# 12_-_MIPI-LVDS-RGB.net
KiCad netlist of a schematic drawn in Altium Designer
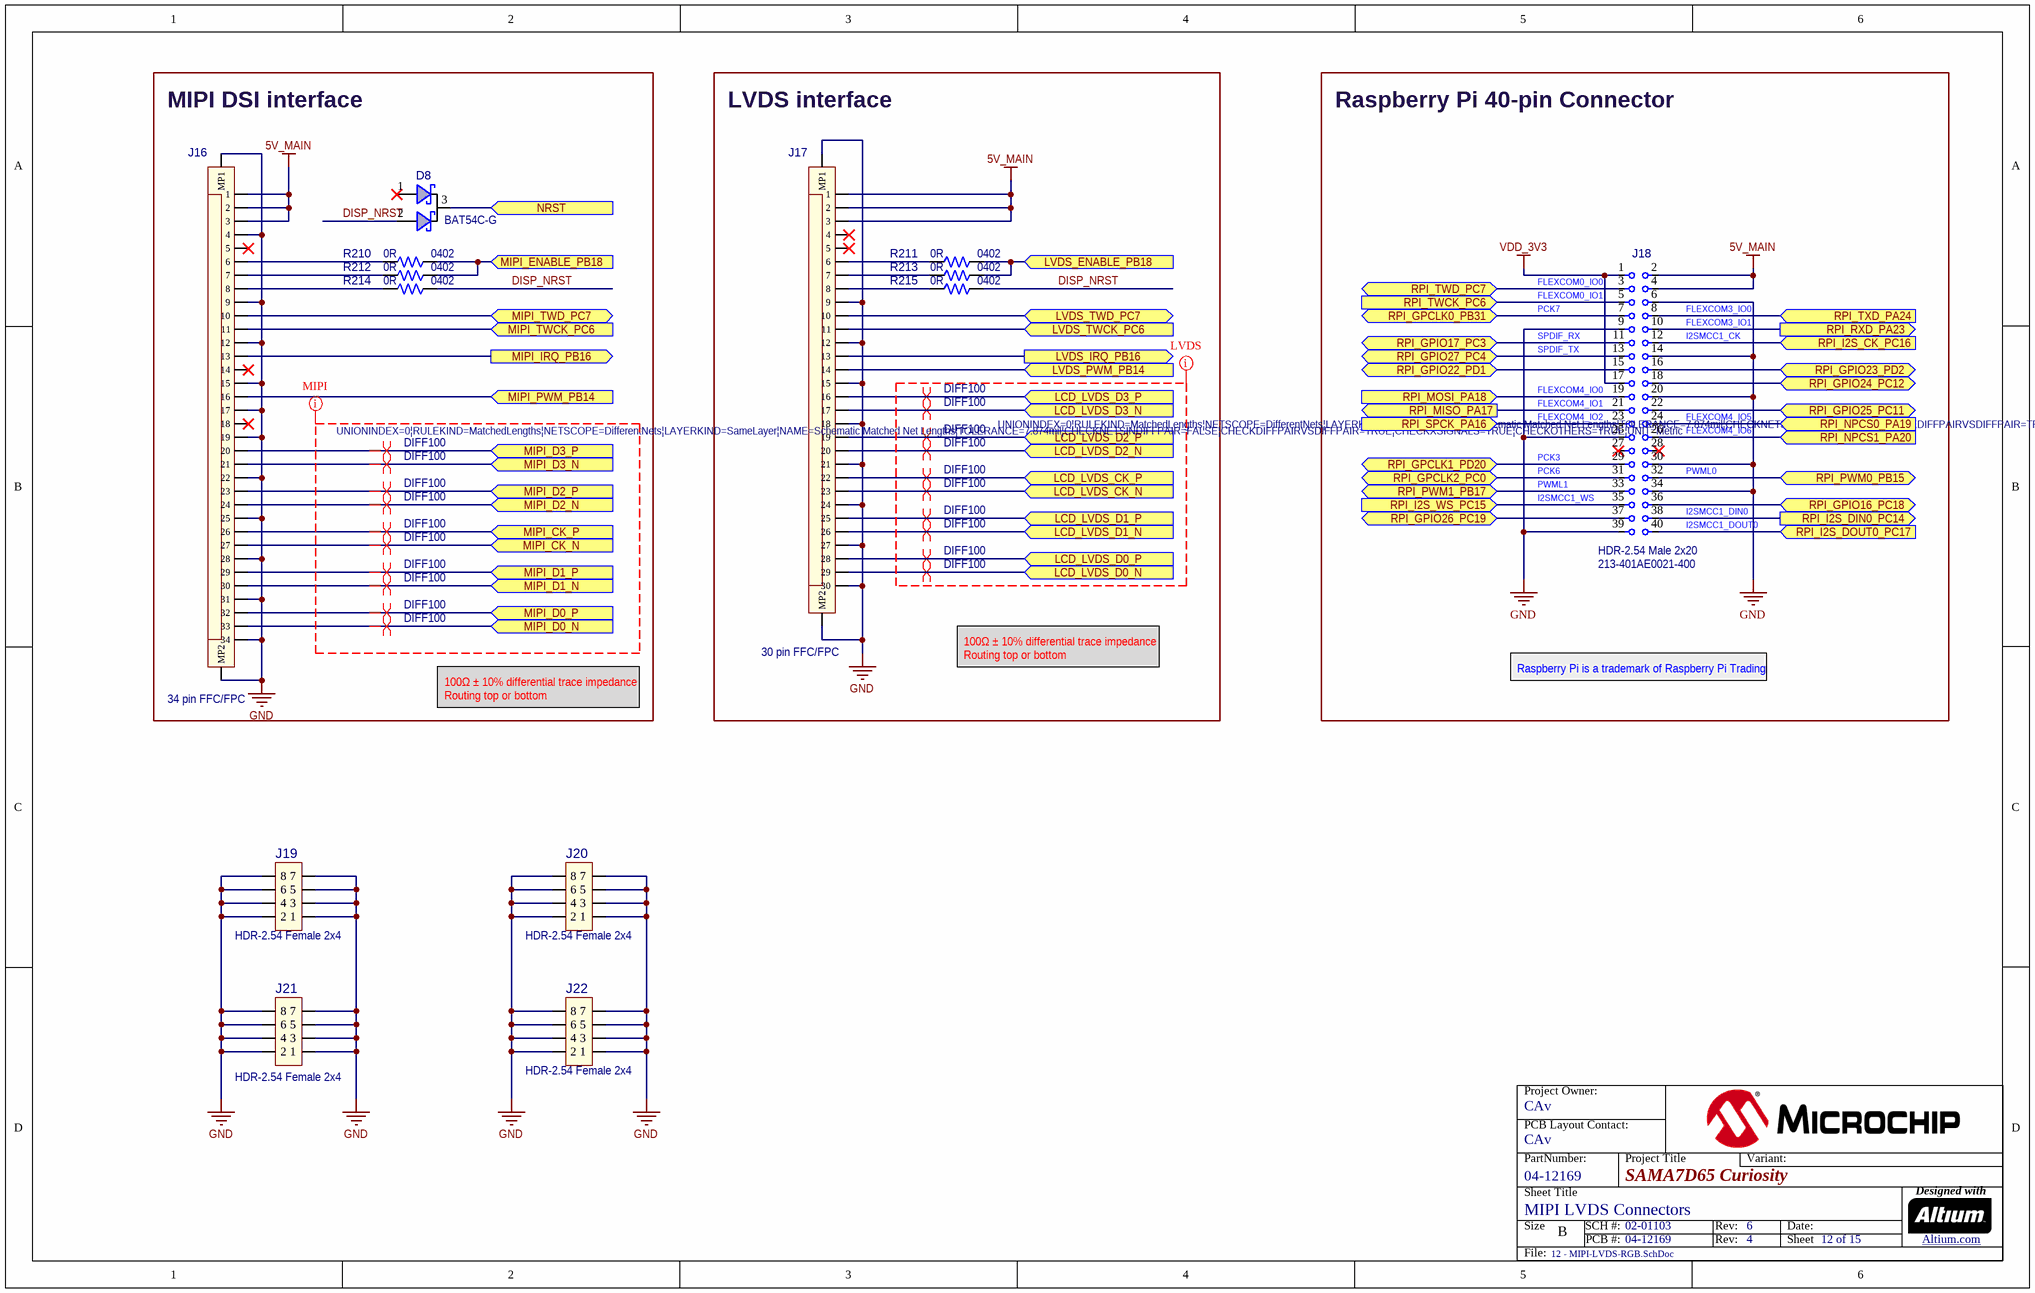
[diagram p0: 12 - MIPI-LVDS-RGB.SchDoc]

(export (version "E")
  (design (tool "Eeschema 10.0.6"))
  (components
    (comp (ref "D8")
      (value "BAT54C-G")
      (footprint "SOT-23-3")
      (fields
        (field (name "POWER") "225mW")
        (field (name "Comment") "Diode Schottky Dual CK")
        (field (name "OWNER") "Cristina Salanti")
      )
      (libsource (lib "MCHP-CDB") (part "Diode Schottky Dual CK"))
    )
    (comp (ref "J16")
      (value "34 pin FFC/FPC")
      (footprint "CON_FPC_0.5_FEMALE_2X17_SMD_AMPHENOL_F314-1A7H1-11034")
      (fields
        (field (name "VOLTAGE") "50V")
        (field (name "Comment") "CON FFC 1x34")
        (field (name "OWNER") "Dragos Danaila")
      )
      (libsource (lib "MCHP-CDB") (part "CON FFC 1x34"))
    )
    (comp (ref "J17")
      (value "30 pin FFC/FPC")
      (footprint "CON_FPC_0.5_FEMALE_2X15_SMD_MLX_52559-3052")
      (fields
        (field (name "VOLTAGE") "50V")
        (field (name "Comment") "CON FFC 1x30")
        (field (name "OWNER") "Dragos Danaila")
      )
      (libsource (lib "MCHP-CDB") (part "CON FFC 1x30"))
    )
    (comp (ref "J18")
      (value "HDR-2.54 Male 2x20")
      (footprint "HDR_M_2.54_2x20")
      (fields
        (field (name "MANUFACTURER PART NUMBER 1") "213-401AE0021-400")
        (field (name "Comment") "Header 2x20")
        (field (name "OWNER") "Stephen Humberd")
      )
      (libsource (lib "MCHP-CDB") (part "Header 2x20"))
    )
    (comp (ref "J19")
      (value "HDR-2.54 Female 2x4")
      (footprint "HDR_F_2.54_2x4")
      (fields (field (name "Comment") "Header 2x4") (field (name "OWNER") "Jamus Griego"))
      (libsource (lib "MCHP-CDB") (part "Header 2x4"))
    )
    (comp (ref "J20")
      (value "HDR-2.54 Female 2x4")
      (footprint "HDR_F_2.54_2x4")
      (fields (field (name "Comment") "Header 2x4") (field (name "OWNER") "Jamus Griego"))
      (libsource (lib "MCHP-CDB") (part "Header 2x4"))
    )
    (comp (ref "J21")
      (value "HDR-2.54 Female 2x4")
      (footprint "HDR_F_2.54_2x4")
      (fields (field (name "Comment") "Header 2x4") (field (name "OWNER") "Jamus Griego"))
      (libsource (lib "MCHP-CDB") (part "Header 2x4"))
    )
    (comp (ref "J22")
      (value "HDR-2.54 Female 2x4")
      (footprint "HDR_F_2.54_2x4")
      (fields (field (name "Comment") "Header 2x4") (field (name "OWNER") "Jamus Griego"))
      (libsource (lib "MCHP-CDB") (part "Header 2x4"))
    )
    (comp (ref "R210")
      (value "0R")
      (footprint "RES_C_0402")
      (description "Resistor")
      (fields
        (field (name "PACKAGE") "0402")
        (field (name "POWER") "1/16W")
        (field (name "OWNER") "Sompoch Loboonlert")
      )
      (libsource (lib "MCHP-CDB") (part "Resistor"))
    )
    (comp (ref "R211")
      (value "0R")
      (footprint "RES_C_0402")
      (description "Resistor")
      (fields
        (field (name "PACKAGE") "0402")
        (field (name "POWER") "1/16W")
        (field (name "OWNER") "Sompoch Loboonlert")
      )
      (libsource (lib "MCHP-CDB") (part "Resistor"))
    )
    (comp (ref "R212")
      (value "0R")
      (footprint "RES_C_0402")
      (description "Resistor")
      (fields
        (field (name "PACKAGE") "0402")
        (field (name "POWER") "1/16W")
        (field (name "OWNER") "Sompoch Loboonlert")
      )
      (libsource (lib "MCHP-CDB") (part "Resistor"))
    )
    (comp (ref "R213")
      (value "0R")
      (footprint "RES_C_0402")
      (description "Resistor")
      (fields
        (field (name "PACKAGE") "0402")
        (field (name "POWER") "1/16W")
        (field (name "OWNER") "Sompoch Loboonlert")
      )
      (libsource (lib "MCHP-CDB") (part "Resistor"))
    )
    (comp (ref "R214")
      (value "0R")
      (footprint "RES_C_0402")
      (description "Resistor")
      (fields
        (field (name "PACKAGE") "0402")
        (field (name "POWER") "1/16W")
        (field (name "OWNER") "Sompoch Loboonlert")
      )
      (libsource (lib "MCHP-CDB") (part "Resistor"))
    )
    (comp (ref "R215")
      (value "0R")
      (footprint "RES_C_0402")
      (description "Resistor")
      (fields
        (field (name "PACKAGE") "0402")
        (field (name "POWER") "1/16W")
        (field (name "OWNER") "Sompoch Loboonlert")
      )
      (libsource (lib "MCHP-CDB") (part "Resistor"))
    )
  )
  (nets
    (net (code "1") (name "/DISP_NRST") (class "Default")
      (node (ref "D8") (pin "2") (pinfunction "A_2") (pintype "passive"))
      (node (ref "R214") (pin "2") (pinfunction "2_2") (pintype "passive"))
      (node (ref "R215") (pin "2") (pinfunction "2_2") (pintype "passive"))
    )
    (net (code "2") (name "/LCD_LVDS_CK_N") (class "Default")
      (node (ref "J17") (pin "23") (pinfunction "23_23") (pintype "passive"))
    )
    (net (code "3") (name "/LCD_LVDS_CK_P") (class "Default")
      (node (ref "J17") (pin "22") (pinfunction "22_22") (pintype "passive"))
    )
    (net (code "4") (name "/LCD_LVDS_D0_N") (class "Default")
      (node (ref "J17") (pin "29") (pinfunction "29_29") (pintype "passive"))
    )
    (net (code "5") (name "/LCD_LVDS_D0_P") (class "Default")
      (node (ref "J17") (pin "28") (pinfunction "28_28") (pintype "passive"))
    )
    (net (code "6") (name "/LCD_LVDS_D1_N") (class "Default")
      (node (ref "J17") (pin "26") (pinfunction "26_26") (pintype "passive"))
    )
    (net (code "7") (name "/LCD_LVDS_D1_P") (class "Default")
      (node (ref "J17") (pin "25") (pinfunction "25_25") (pintype "passive"))
    )
    (net (code "8") (name "/LCD_LVDS_D2_N") (class "Default")
      (node (ref "J17") (pin "20") (pinfunction "20_20") (pintype "passive"))
    )
    (net (code "9") (name "/LCD_LVDS_D2_P") (class "Default")
      (node (ref "J17") (pin "19") (pinfunction "19_19") (pintype "passive"))
    )
    (net (code "10") (name "/LCD_LVDS_D3_N") (class "Default")
      (node (ref "J17") (pin "17") (pinfunction "17_17") (pintype "passive"))
    )
    (net (code "11") (name "/LCD_LVDS_D3_P") (class "Default")
      (node (ref "J17") (pin "16") (pinfunction "16_16") (pintype "passive"))
    )
    (net (code "12") (name "/LVDS_ENABLE_PB18") (class "Default")
      (node (ref "R211") (pin "2") (pinfunction "2_2") (pintype "passive"))
      (node (ref "R213") (pin "2") (pinfunction "2_2") (pintype "passive"))
    )
    (net (code "13") (name "/LVDS_IRQ_PB16") (class "Default")
      (node (ref "J17") (pin "13") (pinfunction "13_13") (pintype "passive"))
    )
    (net (code "14") (name "/LVDS_PWM_PB14") (class "Default")
      (node (ref "J17") (pin "14") (pinfunction "14_14") (pintype "passive"))
    )
    (net (code "15") (name "/LVDS_TWCK_PC6") (class "Default")
      (node (ref "J17") (pin "11") (pinfunction "11_11") (pintype "passive"))
    )
    (net (code "16") (name "/LVDS_TWD_PC7") (class "Default")
      (node (ref "J17") (pin "10") (pinfunction "10_10") (pintype "passive"))
    )
    (net (code "17") (name "/MIPI_CK_N") (class "Default")
      (node (ref "J16") (pin "27") (pinfunction "27_27") (pintype "passive"))
    )
    (net (code "18") (name "/MIPI_CK_P") (class "Default")
      (node (ref "J16") (pin "26") (pinfunction "26_26") (pintype "passive"))
    )
    (net (code "19") (name "/MIPI_D0_N") (class "Default")
      (node (ref "J16") (pin "33") (pinfunction "33_33") (pintype "passive"))
    )
    (net (code "20") (name "/MIPI_D0_P") (class "Default")
      (node (ref "J16") (pin "32") (pinfunction "32_32") (pintype "passive"))
    )
    (net (code "21") (name "/MIPI_D1_N") (class "Default")
      (node (ref "J16") (pin "30") (pinfunction "30_30") (pintype "passive"))
    )
    (net (code "22") (name "/MIPI_D1_P") (class "Default")
      (node (ref "J16") (pin "29") (pinfunction "29_29") (pintype "passive"))
    )
    (net (code "23") (name "/MIPI_D2_N") (class "Default")
      (node (ref "J16") (pin "24") (pinfunction "24_24") (pintype "passive"))
    )
    (net (code "24") (name "/MIPI_D2_P") (class "Default")
      (node (ref "J16") (pin "23") (pinfunction "23_23") (pintype "passive"))
    )
    (net (code "25") (name "/MIPI_D3_N") (class "Default")
      (node (ref "J16") (pin "21") (pinfunction "21_21") (pintype "passive"))
    )
    (net (code "26") (name "/MIPI_D3_P") (class "Default")
      (node (ref "J16") (pin "20") (pinfunction "20_20") (pintype "passive"))
    )
    (net (code "27") (name "/MIPI_ENABLE_PB18") (class "Default")
      (node (ref "R210") (pin "2") (pinfunction "2_2") (pintype "passive"))
      (node (ref "R212") (pin "2") (pinfunction "2_2") (pintype "passive"))
    )
    (net (code "28") (name "/MIPI_IRQ_PB16") (class "Default")
      (node (ref "J16") (pin "13") (pinfunction "13_13") (pintype "passive"))
    )
    (net (code "29") (name "/MIPI_PWM_PB14") (class "Default")
      (node (ref "J16") (pin "16") (pinfunction "16_16") (pintype "passive"))
    )
    (net (code "30") (name "/MIPI_TWCK_PC6") (class "Default")
      (node (ref "J16") (pin "11") (pinfunction "11_11") (pintype "passive"))
    )
    (net (code "31") (name "/MIPI_TWD_PC7") (class "Default")
      (node (ref "J16") (pin "10") (pinfunction "10_10") (pintype "passive"))
    )
    (net (code "32") (name "/NRST") (class "Default")
      (node (ref "D8") (pin "3") (pinfunction "KK_3") (pintype "passive"))
    )
    (net (code "33") (name "/RPI_GPCLK0_PB31") (class "Default")
      (node (ref "J18") (pin "7") (pinfunction "7_7") (pintype "passive"))
    )
    (net (code "34") (name "/RPI_GPCLK1_PD20") (class "Default")
      (node (ref "J18") (pin "29") (pinfunction "29_29") (pintype "passive"))
    )
    (net (code "35") (name "/RPI_GPCLK2_PC0") (class "Default")
      (node (ref "J18") (pin "31") (pinfunction "31_31") (pintype "passive"))
    )
    (net (code "36") (name "/RPI_GPIO16_PC18") (class "Default")
      (node (ref "J18") (pin "36") (pinfunction "36_36") (pintype "passive"))
    )
    (net (code "37") (name "/RPI_GPIO17_PC3") (class "Default")
      (node (ref "J18") (pin "11") (pinfunction "11_11") (pintype "passive"))
    )
    (net (code "38") (name "/RPI_GPIO22_PD1") (class "Default")
      (node (ref "J18") (pin "15") (pinfunction "15_15") (pintype "passive"))
    )
    (net (code "39") (name "/RPI_GPIO23_PD2") (class "Default")
      (node (ref "J18") (pin "16") (pinfunction "16_16") (pintype "passive"))
    )
    (net (code "40") (name "/RPI_GPIO24_PC12") (class "Default")
      (node (ref "J18") (pin "18") (pinfunction "18_18") (pintype "passive"))
    )
    (net (code "41") (name "/RPI_GPIO25_PC11") (class "Default")
      (node (ref "J18") (pin "22") (pinfunction "22_22") (pintype "passive"))
    )
    (net (code "42") (name "/RPI_GPIO26_PC19") (class "Default")
      (node (ref "J18") (pin "37") (pinfunction "37_37") (pintype "passive"))
    )
    (net (code "43") (name "/RPI_GPIO27_PC4") (class "Default")
      (node (ref "J18") (pin "13") (pinfunction "13_13") (pintype "passive"))
    )
    (net (code "44") (name "/RPI_I2S_CK_PC16") (class "Default")
      (node (ref "J18") (pin "12") (pinfunction "12_12") (pintype "passive"))
    )
    (net (code "45") (name "/RPI_I2S_DIN0_PC14") (class "Default")
      (node (ref "J18") (pin "38") (pinfunction "38_38") (pintype "passive"))
    )
    (net (code "46") (name "/RPI_I2S_DOUT0_PC17") (class "Default")
      (node (ref "J18") (pin "40") (pinfunction "40_40") (pintype "passive"))
    )
    (net (code "47") (name "/RPI_I2S_WS_PC15") (class "Default")
      (node (ref "J18") (pin "35") (pinfunction "35_35") (pintype "passive"))
    )
    (net (code "48") (name "/RPI_MISO_PA17") (class "Default")
      (node (ref "J18") (pin "21") (pinfunction "21_21") (pintype "passive"))
    )
    (net (code "49") (name "/RPI_MOSI_PA18") (class "Default")
      (node (ref "J18") (pin "19") (pinfunction "19_19") (pintype "passive"))
    )
    (net (code "50") (name "/RPI_NPCS0_PA19") (class "Default")
      (node (ref "J18") (pin "24") (pinfunction "24_24") (pintype "passive"))
    )
    (net (code "51") (name "/RPI_NPCS1_PA20") (class "Default")
      (node (ref "J18") (pin "26") (pinfunction "26_26") (pintype "passive"))
    )
    (net (code "52") (name "/RPI_PWM0_PB15") (class "Default")
      (node (ref "J18") (pin "32") (pinfunction "32_32") (pintype "passive"))
    )
    (net (code "53") (name "/RPI_PWM1_PB17") (class "Default")
      (node (ref "J18") (pin "33") (pinfunction "33_33") (pintype "passive"))
    )
    (net (code "54") (name "/RPI_RXD_PA23") (class "Default")
      (node (ref "J18") (pin "10") (pinfunction "10_10") (pintype "passive"))
    )
    (net (code "55") (name "/RPI_SPCK_PA16") (class "Default")
      (node (ref "J18") (pin "23") (pinfunction "23_23") (pintype "passive"))
    )
    (net (code "56") (name "/RPI_TWCK_PC6") (class "Default")
      (node (ref "J18") (pin "5") (pinfunction "5_5") (pintype "passive"))
    )
    (net (code "57") (name "/RPI_TWD_PC7") (class "Default")
      (node (ref "J18") (pin "3") (pinfunction "3_3") (pintype "passive"))
    )
    (net (code "58") (name "/RPI_TXD_PA24") (class "Default")
      (node (ref "J18") (pin "8") (pinfunction "8_8") (pintype "passive"))
    )
    (net (code "59") (name "5V_MAIN") (class "Default")
      (node (ref "J16") (pin "1") (pinfunction "1_1") (pintype "passive"))
      (node (ref "J16") (pin "2") (pinfunction "2_2") (pintype "passive"))
      (node (ref "J16") (pin "3") (pinfunction "3_3") (pintype "passive"))
      (node (ref "J17") (pin "1") (pinfunction "1_1") (pintype "passive"))
      (node (ref "J17") (pin "2") (pinfunction "2_2") (pintype "passive"))
      (node (ref "J17") (pin "3") (pinfunction "3_3") (pintype "passive"))
      (node (ref "J18") (pin "2") (pinfunction "2_2") (pintype "passive"))
      (node (ref "J18") (pin "4") (pinfunction "4_4") (pintype "passive"))
    )
    (net (code "60") (name "GND") (class "Default")
      (node (ref "J16") (pin "12") (pinfunction "12_12") (pintype "passive"))
      (node (ref "J16") (pin "15") (pinfunction "15_15") (pintype "passive"))
      (node (ref "J16") (pin "17") (pinfunction "17_17") (pintype "passive"))
      (node (ref "J16") (pin "19") (pinfunction "19_19") (pintype "passive"))
      (node (ref "J16") (pin "22") (pinfunction "22_22") (pintype "passive"))
      (node (ref "J16") (pin "25") (pinfunction "25_25") (pintype "passive"))
      (node (ref "J16") (pin "28") (pinfunction "28_28") (pintype "passive"))
      (node (ref "J16") (pin "31") (pinfunction "31_31") (pintype "passive"))
      (node (ref "J16") (pin "34") (pinfunction "34_34") (pintype "passive"))
      (node (ref "J16") (pin "4") (pinfunction "4_4") (pintype "passive"))
      (node (ref "J16") (pin "9") (pinfunction "9_9") (pintype "passive"))
      (node (ref "J16") (pin "MP1") (pinfunction "MP1_MP1") (pintype "passive"))
      (node (ref "J16") (pin "MP2") (pinfunction "MP2_MP2") (pintype "passive"))
      (node (ref "J17") (pin "12") (pinfunction "12_12") (pintype "passive"))
      (node (ref "J17") (pin "15") (pinfunction "15_15") (pintype "passive"))
      (node (ref "J17") (pin "18") (pinfunction "18_18") (pintype "passive"))
      (node (ref "J17") (pin "21") (pinfunction "21_21") (pintype "passive"))
      (node (ref "J17") (pin "24") (pinfunction "24_24") (pintype "passive"))
      (node (ref "J17") (pin "27") (pinfunction "27_27") (pintype "passive"))
      (node (ref "J17") (pin "30") (pinfunction "30_30") (pintype "passive"))
      (node (ref "J17") (pin "9") (pinfunction "9_9") (pintype "passive"))
      (node (ref "J17") (pin "MP1") (pinfunction "MP1_MP1") (pintype "passive"))
      (node (ref "J17") (pin "MP2") (pinfunction "MP2_MP2") (pintype "passive"))
      (node (ref "J18") (pin "14") (pinfunction "14_14") (pintype "passive"))
      (node (ref "J18") (pin "20") (pinfunction "20_20") (pintype "passive"))
      (node (ref "J18") (pin "25") (pinfunction "25_25") (pintype "passive"))
      (node (ref "J18") (pin "30") (pinfunction "30_30") (pintype "passive"))
      (node (ref "J18") (pin "34") (pinfunction "34_34") (pintype "passive"))
      (node (ref "J18") (pin "39") (pinfunction "39_39") (pintype "passive"))
      (node (ref "J18") (pin "6") (pinfunction "6_6") (pintype "passive"))
      (node (ref "J18") (pin "9") (pinfunction "9_9") (pintype "passive"))
      (node (ref "J19") (pin "1") (pinfunction "1_1") (pintype "passive"))
      (node (ref "J19") (pin "2") (pinfunction "2_2") (pintype "passive"))
      (node (ref "J19") (pin "3") (pinfunction "3_3") (pintype "passive"))
      (node (ref "J19") (pin "4") (pinfunction "4_4") (pintype "passive"))
      (node (ref "J19") (pin "5") (pinfunction "5_5") (pintype "passive"))
      (node (ref "J19") (pin "6") (pinfunction "6_6") (pintype "passive"))
      (node (ref "J19") (pin "7") (pinfunction "7_7") (pintype "passive"))
      (node (ref "J19") (pin "8") (pinfunction "8_8") (pintype "passive"))
      (node (ref "J20") (pin "1") (pinfunction "1_1") (pintype "passive"))
      (node (ref "J20") (pin "2") (pinfunction "2_2") (pintype "passive"))
      (node (ref "J20") (pin "3") (pinfunction "3_3") (pintype "passive"))
      (node (ref "J20") (pin "4") (pinfunction "4_4") (pintype "passive"))
      (node (ref "J20") (pin "5") (pinfunction "5_5") (pintype "passive"))
      (node (ref "J20") (pin "6") (pinfunction "6_6") (pintype "passive"))
      (node (ref "J20") (pin "7") (pinfunction "7_7") (pintype "passive"))
      (node (ref "J20") (pin "8") (pinfunction "8_8") (pintype "passive"))
      (node (ref "J21") (pin "1") (pinfunction "1_1") (pintype "passive"))
      (node (ref "J21") (pin "2") (pinfunction "2_2") (pintype "passive"))
      (node (ref "J21") (pin "3") (pinfunction "3_3") (pintype "passive"))
      (node (ref "J21") (pin "4") (pinfunction "4_4") (pintype "passive"))
      (node (ref "J21") (pin "5") (pinfunction "5_5") (pintype "passive"))
      (node (ref "J21") (pin "6") (pinfunction "6_6") (pintype "passive"))
      (node (ref "J21") (pin "7") (pinfunction "7_7") (pintype "passive"))
      (node (ref "J21") (pin "8") (pinfunction "8_8") (pintype "passive"))
      (node (ref "J22") (pin "1") (pinfunction "1_1") (pintype "passive"))
      (node (ref "J22") (pin "2") (pinfunction "2_2") (pintype "passive"))
      (node (ref "J22") (pin "3") (pinfunction "3_3") (pintype "passive"))
      (node (ref "J22") (pin "4") (pinfunction "4_4") (pintype "passive"))
      (node (ref "J22") (pin "5") (pinfunction "5_5") (pintype "passive"))
      (node (ref "J22") (pin "6") (pinfunction "6_6") (pintype "passive"))
      (node (ref "J22") (pin "7") (pinfunction "7_7") (pintype "passive"))
      (node (ref "J22") (pin "8") (pinfunction "8_8") (pintype "passive"))
    )
    (net (code "61") (name "Net-(J16-Pad6)") (class "Default")
      (node (ref "J16") (pin "6") (pinfunction "6_6") (pintype "passive"))
      (node (ref "R210") (pin "1") (pinfunction "1_1") (pintype "passive"))
    )
    (net (code "62") (name "Net-(J16-Pad7)") (class "Default")
      (node (ref "J16") (pin "7") (pinfunction "7_7") (pintype "passive"))
      (node (ref "R212") (pin "1") (pinfunction "1_1") (pintype "passive"))
    )
    (net (code "63") (name "Net-(J16-Pad8)") (class "Default")
      (node (ref "J16") (pin "8") (pinfunction "8_8") (pintype "passive"))
      (node (ref "R214") (pin "1") (pinfunction "1_1") (pintype "passive"))
    )
    (net (code "64") (name "Net-(J17-Pad6)") (class "Default")
      (node (ref "J17") (pin "6") (pinfunction "6_6") (pintype "passive"))
      (node (ref "R211") (pin "1") (pinfunction "1_1") (pintype "passive"))
    )
    (net (code "65") (name "Net-(J17-Pad7)") (class "Default")
      (node (ref "J17") (pin "7") (pinfunction "7_7") (pintype "passive"))
      (node (ref "R213") (pin "1") (pinfunction "1_1") (pintype "passive"))
    )
    (net (code "66") (name "Net-(J17-Pad8)") (class "Default")
      (node (ref "J17") (pin "8") (pinfunction "8_8") (pintype "passive"))
      (node (ref "R215") (pin "1") (pinfunction "1_1") (pintype "passive"))
    )
    (net (code "67") (name "VDD_3V3") (class "Default")
      (node (ref "J18") (pin "1") (pinfunction "1_1") (pintype "passive"))
      (node (ref "J18") (pin "17") (pinfunction "17_17") (pintype "passive"))
    )
    (net (code "68") (name "unconnected-(D8-A-Pad1)") (class "Default")
      (node (ref "D8") (pin "1") (pinfunction "A_1") (pintype "passive+no_connect"))
    )
    (net (code "69") (name "unconnected-(J16-Pad5)") (class "Default")
      (node (ref "J16") (pin "5") (pinfunction "5_5") (pintype "passive+no_connect"))
    )
    (net (code "70") (name "unconnected-(J16-Pad14)") (class "Default")
      (node (ref "J16") (pin "14") (pinfunction "14_14") (pintype "passive+no_connect"))
    )
    (net (code "71") (name "unconnected-(J16-Pad18)") (class "Default")
      (node (ref "J16") (pin "18") (pinfunction "18_18") (pintype "passive+no_connect"))
    )
    (net (code "72") (name "unconnected-(J17-Pad4)") (class "Default")
      (node (ref "J17") (pin "4") (pinfunction "4_4") (pintype "passive+no_connect"))
    )
    (net (code "73") (name "unconnected-(J17-Pad5)") (class "Default")
      (node (ref "J17") (pin "5") (pinfunction "5_5") (pintype "passive+no_connect"))
    )
    (net (code "74") (name "unconnected-(J18-Pad27)") (class "Default")
      (node (ref "J18") (pin "27") (pinfunction "27_27") (pintype "passive+no_connect"))
    )
    (net (code "75") (name "unconnected-(J18-Pad28)") (class "Default")
      (node (ref "J18") (pin "28") (pinfunction "28_28") (pintype "passive+no_connect"))
    )
  )
)
